# MegaBot.net
KiCad netlist of a schematic drawn in EAGLE
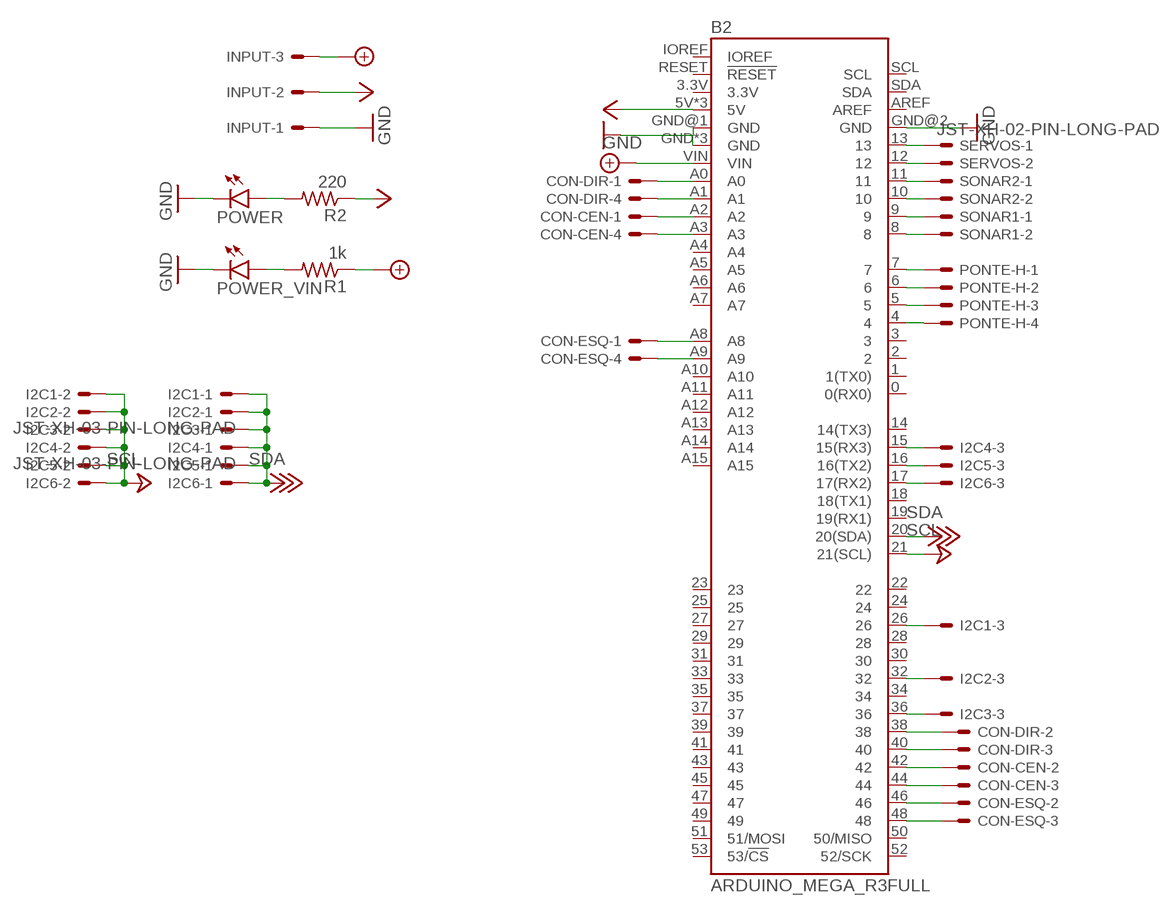
[diagram p0: schematic, sheet 1]

(export (version "E")
  (design (tool "Eeschema 10.0.6"))
  (components
    (comp (ref "B2")
      (value "ARDUINO_MEGA_R3FULL")
      (footprint "eagle-import:ARDUINO_MEGA_NO_SILK")
      (libsource (lib "eagle-import") (part "ARDUINO_MEGA_R3FULL"))
    )
    (comp (ref "CON-CEN")
      (value "JST-XH-04-PIN-LONG-PAD")
      (footprint "eagle-import:JST-XH-04-PACKAGE-LONG-PAD")
      (libsource (lib "eagle-import") (part "JST-XH-04-PIN-LONG-PAD"))
    )
    (comp (ref "CON-DIR")
      (value "JST-XH-04-PIN-LONG-PAD")
      (footprint "eagle-import:JST-XH-04-PACKAGE-LONG-PAD")
      (libsource (lib "eagle-import") (part "JST-XH-04-PIN-LONG-PAD"))
    )
    (comp (ref "CON-ESQ")
      (value "JST-XH-04-PIN-LONG-PAD")
      (footprint "eagle-import:JST-XH-04-PACKAGE-LONG-PAD")
      (libsource (lib "eagle-import") (part "JST-XH-04-PIN-LONG-PAD"))
    )
    (comp (ref "I2C1")
      (value "JST-XH-03-PIN-LONG-PAD")
      (footprint "eagle-import:JST-XH-03-PACKAGE-LONG-PAD")
      (libsource (lib "eagle-import") (part "JST-XH-03-PIN-LONG-PAD"))
    )
    (comp (ref "I2C2")
      (value "JST-XH-03-PIN-LONG-PAD")
      (footprint "eagle-import:JST-XH-03-PACKAGE-LONG-PAD")
      (libsource (lib "eagle-import") (part "JST-XH-03-PIN-LONG-PAD"))
    )
    (comp (ref "I2C3")
      (value "JST-XH-03-PIN-LONG-PAD")
      (footprint "eagle-import:JST-XH-03-PACKAGE-LONG-PAD")
      (libsource (lib "eagle-import") (part "JST-XH-03-PIN-LONG-PAD"))
    )
    (comp (ref "I2C4")
      (value "JST-XH-03-PIN-LONG-PAD")
      (footprint "eagle-import:JST-XH-03-PACKAGE-LONG-PAD")
      (libsource (lib "eagle-import") (part "JST-XH-03-PIN-LONG-PAD"))
    )
    (comp (ref "I2C5")
      (value "JST-XH-03-PIN-LONG-PAD")
      (footprint "eagle-import:JST-XH-03-PACKAGE-LONG-PAD")
      (libsource (lib "eagle-import") (part "JST-XH-03-PIN-LONG-PAD"))
    )
    (comp (ref "I2C6")
      (value "JST-XH-03-PIN-LONG-PAD")
      (footprint "eagle-import:JST-XH-03-PACKAGE-LONG-PAD")
      (libsource (lib "eagle-import") (part "JST-XH-03-PIN-LONG-PAD"))
    )
    (comp (ref "INPUT")
      (value "KK-156-3")
      (footprint "eagle-import:KK-156-3")
      (fields (field (name "MF") "MOLEX"))
      (libsource (lib "eagle-import") (part "KK-156-3"))
    )
    (comp (ref "PONTE-H")
      (value "JST-XH-04-PIN-LONG-PAD")
      (footprint "eagle-import:JST-XH-04-PACKAGE-LONG-PAD")
      (libsource (lib "eagle-import") (part "JST-XH-04-PIN-LONG-PAD"))
    )
    (comp (ref "POWER")
      (value "LEDLED5MM_LONG_PAD")
      (footprint "eagle-import:LED5MM_LONG_PAD")
      (libsource (lib "eagle-import") (part "LEDLED5MM_LONG_PAD"))
    )
    (comp (ref "POWER_VIN")
      (value "LEDLED5MM_LONG_PAD")
      (footprint "eagle-import:LED5MM_LONG_PAD")
      (libsource (lib "eagle-import") (part "LEDLED5MM_LONG_PAD"))
    )
    (comp (ref "R1")
      (value "1k")
      (footprint "eagle-import:0204_7")
      (libsource (lib "eagle-import") (part "R-US_0204/7"))
    )
    (comp (ref "R2")
      (value "220")
      (footprint "eagle-import:0204_7")
      (libsource (lib "eagle-import") (part "R-US_0204/7"))
    )
    (comp (ref "SERVOS")
      (value "JST-XH-02-PIN-LONG-PAD")
      (footprint "eagle-import:JST-XH-02-PACKAGE-LONG-PAD")
      (libsource (lib "eagle-import") (part "JST-XH-02-PIN-LONG-PAD"))
    )
    (comp (ref "SONAR1")
      (value "JST-XH-02-PIN-LONG-PAD")
      (footprint "eagle-import:JST-XH-02-PACKAGE-LONG-PAD")
      (libsource (lib "eagle-import") (part "JST-XH-02-PIN-LONG-PAD"))
    )
    (comp (ref "SONAR2")
      (value "JST-XH-02-PIN-LONG-PAD")
      (footprint "eagle-import:JST-XH-02-PACKAGE-LONG-PAD")
      (libsource (lib "eagle-import") (part "JST-XH-02-PIN-LONG-PAD"))
    )
  )
  (nets
    (net (code "1") (name "+8V") (class "Default")
      (node (ref "B2") (pin "VIN") (pinfunction "VIN_VIN") (pintype "bidirectional"))
      (node (ref "INPUT") (pin "3") (pinfunction "S_3") (pintype "passive"))
      (node (ref "R1") (pin "1") (pinfunction "1_1") (pintype "passive"))
    )
    (net (code "2") (name "GND") (class "Default")
      (node (ref "B2") (pin "GND") (pinfunction "GND_GND") (pintype "bidirectional"))
      (node (ref "B2") (pin "GND@1") (pinfunction "GND_GND@1") (pintype "bidirectional"))
      (node (ref "B2") (pin "GND@2") (pinfunction "GND_GND@2") (pintype "bidirectional"))
      (node (ref "B2") (pin "GND@3") (pinfunction "GND_GND@3") (pintype "bidirectional"))
      (node (ref "B2") (pin "GND@4") (pinfunction "GND_GND@4") (pintype "bidirectional"))
      (node (ref "INPUT") (pin "1") (pinfunction "S_1") (pintype "passive"))
      (node (ref "POWER") (pin "K") (pinfunction "C_K") (pintype "passive"))
      (node (ref "POWER_VIN") (pin "K") (pinfunction "C_K") (pintype "passive"))
    )
    (net (code "3") (name "Net-(B2-15(RX3))") (class "Default")
      (node (ref "B2") (pin "15") (pinfunction "15(RX3)_15") (pintype "bidirectional"))
      (node (ref "I2C4") (pin "3") (pinfunction "S_3") (pintype "passive"))
    )
    (net (code "4") (name "Net-(B2-16(TX2))") (class "Default")
      (node (ref "B2") (pin "16") (pinfunction "16(TX2)_16") (pintype "bidirectional"))
      (node (ref "I2C5") (pin "3") (pinfunction "S_3") (pintype "passive"))
    )
    (net (code "5") (name "Net-(B2-17(RX2))") (class "Default")
      (node (ref "B2") (pin "17") (pinfunction "17(RX2)_17") (pintype "bidirectional"))
      (node (ref "I2C6") (pin "3") (pinfunction "S_3") (pintype "passive"))
    )
    (net (code "6") (name "Net-(CON-CENA-S)") (class "Default")
      (node (ref "B2") (pin "A2") (pinfunction "A2_A2") (pintype "bidirectional"))
      (node (ref "CON-CEN") (pin "1") (pinfunction "S_1") (pintype "passive"))
    )
    (net (code "7") (name "Net-(CON-CENB-S)") (class "Default")
      (node (ref "B2") (pin "42") (pinfunction "42_42") (pintype "bidirectional"))
      (node (ref "CON-CEN") (pin "2") (pinfunction "S_2") (pintype "passive"))
    )
    (net (code "8") (name "Net-(CON-CENC-S)") (class "Default")
      (node (ref "B2") (pin "44") (pinfunction "44_44") (pintype "bidirectional"))
      (node (ref "CON-CEN") (pin "3") (pinfunction "S_3") (pintype "passive"))
    )
    (net (code "9") (name "Net-(CON-CEND-S)") (class "Default")
      (node (ref "B2") (pin "A3") (pinfunction "A3_A3") (pintype "bidirectional"))
      (node (ref "CON-CEN") (pin "4") (pinfunction "S_4") (pintype "passive"))
    )
    (net (code "10") (name "Net-(CON-DIRA-S)") (class "Default")
      (node (ref "B2") (pin "A0") (pinfunction "A0_A0") (pintype "bidirectional"))
      (node (ref "CON-DIR") (pin "1") (pinfunction "S_1") (pintype "passive"))
    )
    (net (code "11") (name "Net-(CON-DIRB-S)") (class "Default")
      (node (ref "B2") (pin "38") (pinfunction "38_38") (pintype "bidirectional"))
      (node (ref "CON-DIR") (pin "2") (pinfunction "S_2") (pintype "passive"))
    )
    (net (code "12") (name "Net-(CON-DIRC-S)") (class "Default")
      (node (ref "B2") (pin "40") (pinfunction "40_40") (pintype "bidirectional"))
      (node (ref "CON-DIR") (pin "3") (pinfunction "S_3") (pintype "passive"))
    )
    (net (code "13") (name "Net-(CON-DIRD-S)") (class "Default")
      (node (ref "B2") (pin "A1") (pinfunction "A1_A1") (pintype "bidirectional"))
      (node (ref "CON-DIR") (pin "4") (pinfunction "S_4") (pintype "passive"))
    )
    (net (code "14") (name "Net-(CON-ESQA-S)") (class "Default")
      (node (ref "B2") (pin "A8") (pinfunction "A8_A8") (pintype "bidirectional"))
      (node (ref "CON-ESQ") (pin "1") (pinfunction "S_1") (pintype "passive"))
    )
    (net (code "15") (name "Net-(CON-ESQB-S)") (class "Default")
      (node (ref "B2") (pin "46") (pinfunction "46_46") (pintype "bidirectional"))
      (node (ref "CON-ESQ") (pin "2") (pinfunction "S_2") (pintype "passive"))
    )
    (net (code "16") (name "Net-(CON-ESQC-S)") (class "Default")
      (node (ref "B2") (pin "48") (pinfunction "48_48") (pintype "bidirectional"))
      (node (ref "CON-ESQ") (pin "3") (pinfunction "S_3") (pintype "passive"))
    )
    (net (code "17") (name "Net-(CON-ESQD-S)") (class "Default")
      (node (ref "B2") (pin "A9") (pinfunction "A9_A9") (pintype "bidirectional"))
      (node (ref "CON-ESQ") (pin "4") (pinfunction "S_4") (pintype "passive"))
    )
    (net (code "18") (name "Net-(I2C1C-S)") (class "Default")
      (node (ref "B2") (pin "26") (pinfunction "26_26") (pintype "bidirectional"))
      (node (ref "I2C1") (pin "3") (pinfunction "S_3") (pintype "passive"))
    )
    (net (code "19") (name "Net-(I2C2C-S)") (class "Default")
      (node (ref "B2") (pin "32") (pinfunction "32_32") (pintype "bidirectional"))
      (node (ref "I2C2") (pin "3") (pinfunction "S_3") (pintype "passive"))
    )
    (net (code "20") (name "Net-(I2C3C-S)") (class "Default")
      (node (ref "B2") (pin "36") (pinfunction "36_36") (pintype "bidirectional"))
      (node (ref "I2C3") (pin "3") (pinfunction "S_3") (pintype "passive"))
    )
    (net (code "21") (name "Net-(PONTE-HA-S)") (class "Default")
      (node (ref "B2") (pin "7") (pinfunction "7_7") (pintype "bidirectional"))
      (node (ref "PONTE-H") (pin "1") (pinfunction "S_1") (pintype "passive"))
    )
    (net (code "22") (name "Net-(PONTE-HB-S)") (class "Default")
      (node (ref "B2") (pin "6") (pinfunction "6_6") (pintype "bidirectional"))
      (node (ref "PONTE-H") (pin "2") (pinfunction "S_2") (pintype "passive"))
    )
    (net (code "23") (name "Net-(PONTE-HC-S)") (class "Default")
      (node (ref "B2") (pin "5") (pinfunction "5_5") (pintype "bidirectional"))
      (node (ref "PONTE-H") (pin "3") (pinfunction "S_3") (pintype "passive"))
    )
    (net (code "24") (name "Net-(PONTE-HD-S)") (class "Default")
      (node (ref "B2") (pin "4") (pinfunction "4_4") (pintype "bidirectional"))
      (node (ref "PONTE-H") (pin "4") (pinfunction "S_4") (pintype "passive"))
    )
    (net (code "25") (name "Net-(POWER-PadA)") (class "Default")
      (node (ref "POWER") (pin "A") (pinfunction "A_A") (pintype "passive"))
      (node (ref "R2") (pin "2") (pinfunction "2_2") (pintype "passive"))
    )
    (net (code "26") (name "Net-(POWER_VIN-PadA)") (class "Default")
      (node (ref "POWER_VIN") (pin "A") (pinfunction "A_A") (pintype "passive"))
      (node (ref "R1") (pin "2") (pinfunction "2_2") (pintype "passive"))
    )
    (net (code "27") (name "Net-(SERVOSA-S)") (class "Default")
      (node (ref "B2") (pin "13") (pinfunction "13_13") (pintype "bidirectional"))
      (node (ref "SERVOS") (pin "1") (pinfunction "S_1") (pintype "passive"))
    )
    (net (code "28") (name "Net-(SERVOSB-S)") (class "Default")
      (node (ref "B2") (pin "12") (pinfunction "12_12") (pintype "bidirectional"))
      (node (ref "SERVOS") (pin "2") (pinfunction "S_2") (pintype "passive"))
    )
    (net (code "29") (name "Net-(SONAR1A-S)") (class "Default")
      (node (ref "B2") (pin "9") (pinfunction "9_9") (pintype "bidirectional"))
      (node (ref "SONAR1") (pin "1") (pinfunction "S_1") (pintype "passive"))
    )
    (net (code "30") (name "Net-(SONAR1B-S)") (class "Default")
      (node (ref "B2") (pin "8") (pinfunction "8_8") (pintype "bidirectional"))
      (node (ref "SONAR1") (pin "2") (pinfunction "S_2") (pintype "passive"))
    )
    (net (code "31") (name "Net-(SONAR2A-S)") (class "Default")
      (node (ref "B2") (pin "11") (pinfunction "11_11") (pintype "bidirectional"))
      (node (ref "SONAR2") (pin "1") (pinfunction "S_1") (pintype "passive"))
    )
    (net (code "32") (name "Net-(SONAR2B-S)") (class "Default")
      (node (ref "B2") (pin "10") (pinfunction "10_10") (pintype "bidirectional"))
      (node (ref "SONAR2") (pin "2") (pinfunction "S_2") (pintype "passive"))
    )
    (net (code "33") (name "SCL") (class "Default")
      (node (ref "B2") (pin "21") (pinfunction "21(SCL)_21") (pintype "bidirectional"))
      (node (ref "I2C1") (pin "2") (pinfunction "S_2") (pintype "passive"))
      (node (ref "I2C2") (pin "2") (pinfunction "S_2") (pintype "passive"))
      (node (ref "I2C3") (pin "2") (pinfunction "S_2") (pintype "passive"))
      (node (ref "I2C4") (pin "2") (pinfunction "S_2") (pintype "passive"))
      (node (ref "I2C5") (pin "2") (pinfunction "S_2") (pintype "passive"))
      (node (ref "I2C6") (pin "2") (pinfunction "S_2") (pintype "passive"))
    )
    (net (code "34") (name "SDA") (class "Default")
      (node (ref "B2") (pin "20") (pinfunction "20(SDA)_20") (pintype "bidirectional"))
      (node (ref "I2C1") (pin "1") (pinfunction "S_1") (pintype "passive"))
      (node (ref "I2C2") (pin "1") (pinfunction "S_1") (pintype "passive"))
      (node (ref "I2C3") (pin "1") (pinfunction "S_1") (pintype "passive"))
      (node (ref "I2C4") (pin "1") (pinfunction "S_1") (pintype "passive"))
      (node (ref "I2C5") (pin "1") (pinfunction "S_1") (pintype "passive"))
      (node (ref "I2C6") (pin "1") (pinfunction "S_1") (pintype "passive"))
    )
    (net (code "35") (name "VCC") (class "Default")
      (node (ref "B2") (pin "5V") (pinfunction "5V_5V") (pintype "bidirectional"))
      (node (ref "B2") (pin "5V@1") (pinfunction "5V_5V@1") (pintype "bidirectional"))
      (node (ref "B2") (pin "5V@2") (pinfunction "5V_5V@2") (pintype "bidirectional"))
      (node (ref "INPUT") (pin "2") (pinfunction "S_2") (pintype "passive"))
      (node (ref "R2") (pin "1") (pinfunction "1_1") (pintype "passive"))
    )
    (net (code "36") (name "unconnected-(B2-0(RX0)-Pad0)") (class "Default")
      (node (ref "B2") (pin "0") (pinfunction "0(RX0)_0") (pintype "bidirectional"))
    )
    (net (code "37") (name "unconnected-(B2-1(TX0)-Pad1)") (class "Default")
      (node (ref "B2") (pin "1") (pinfunction "1(TX0)_1") (pintype "bidirectional"))
    )
    (net (code "38") (name "unconnected-(B2-14(TX3)-Pad14)") (class "Default")
      (node (ref "B2") (pin "14") (pinfunction "14(TX3)_14") (pintype "bidirectional"))
    )
    (net (code "39") (name "unconnected-(B2-18(TX1)-Pad18)") (class "Default")
      (node (ref "B2") (pin "18") (pinfunction "18(TX1)_18") (pintype "bidirectional"))
    )
    (net (code "40") (name "unconnected-(B2-19(RX1)-Pad19)") (class "Default")
      (node (ref "B2") (pin "19") (pinfunction "19(RX1)_19") (pintype "bidirectional"))
    )
    (net (code "41") (name "unconnected-(B2-50{slash}MISO-Pad50)") (class "Default")
      (node (ref "B2") (pin "50") (pinfunction "50/MISO_50") (pintype "bidirectional"))
    )
    (net (code "42") (name "unconnected-(B2-51{slash}MOSI-Pad51)") (class "Default")
      (node (ref "B2") (pin "51") (pinfunction "51/MOSI_51") (pintype "bidirectional"))
    )
    (net (code "43") (name "unconnected-(B2-52{slash}SCK-Pad52)") (class "Default")
      (node (ref "B2") (pin "52") (pinfunction "52/SCK_52") (pintype "bidirectional"))
    )
    (net (code "44") (name "unconnected-(B2-53{slash}~{CS}-Pad53)") (class "Default")
      (node (ref "B2") (pin "53") (pinfunction "53/~{CS}_53") (pintype "bidirectional"))
    )
    (net (code "45") (name "unconnected-(B2-Pad2)") (class "Default")
      (node (ref "B2") (pin "2") (pinfunction "2_2") (pintype "bidirectional"))
    )
    (net (code "46") (name "unconnected-(B2-Pad3)") (class "Default")
      (node (ref "B2") (pin "3") (pinfunction "3_3") (pintype "bidirectional"))
    )
    (net (code "47") (name "unconnected-(B2-Pad3.3V)") (class "Default")
      (node (ref "B2") (pin "3.3V") (pinfunction "3.3V_3.3V") (pintype "bidirectional"))
    )
    (net (code "48") (name "unconnected-(B2-Pad22)") (class "Default")
      (node (ref "B2") (pin "22") (pinfunction "22_22") (pintype "bidirectional"))
    )
    (net (code "49") (name "unconnected-(B2-Pad23)") (class "Default")
      (node (ref "B2") (pin "23") (pinfunction "23_23") (pintype "bidirectional"))
    )
    (net (code "50") (name "unconnected-(B2-Pad24)") (class "Default")
      (node (ref "B2") (pin "24") (pinfunction "24_24") (pintype "bidirectional"))
    )
    (net (code "51") (name "unconnected-(B2-Pad25)") (class "Default")
      (node (ref "B2") (pin "25") (pinfunction "25_25") (pintype "bidirectional"))
    )
    (net (code "52") (name "unconnected-(B2-Pad27)") (class "Default")
      (node (ref "B2") (pin "27") (pinfunction "27_27") (pintype "bidirectional"))
    )
    (net (code "53") (name "unconnected-(B2-Pad28)") (class "Default")
      (node (ref "B2") (pin "28") (pinfunction "28_28") (pintype "bidirectional"))
    )
    (net (code "54") (name "unconnected-(B2-Pad29)") (class "Default")
      (node (ref "B2") (pin "29") (pinfunction "29_29") (pintype "bidirectional"))
    )
    (net (code "55") (name "unconnected-(B2-Pad30)") (class "Default")
      (node (ref "B2") (pin "30") (pinfunction "30_30") (pintype "bidirectional"))
    )
    (net (code "56") (name "unconnected-(B2-Pad31)") (class "Default")
      (node (ref "B2") (pin "31") (pinfunction "31_31") (pintype "bidirectional"))
    )
    (net (code "57") (name "unconnected-(B2-Pad33)") (class "Default")
      (node (ref "B2") (pin "33") (pinfunction "33_33") (pintype "bidirectional"))
    )
    (net (code "58") (name "unconnected-(B2-Pad34)") (class "Default")
      (node (ref "B2") (pin "34") (pinfunction "34_34") (pintype "bidirectional"))
    )
    (net (code "59") (name "unconnected-(B2-Pad35)") (class "Default")
      (node (ref "B2") (pin "35") (pinfunction "35_35") (pintype "bidirectional"))
    )
    (net (code "60") (name "unconnected-(B2-Pad37)") (class "Default")
      (node (ref "B2") (pin "37") (pinfunction "37_37") (pintype "bidirectional"))
    )
    (net (code "61") (name "unconnected-(B2-Pad39)") (class "Default")
      (node (ref "B2") (pin "39") (pinfunction "39_39") (pintype "bidirectional"))
    )
    (net (code "62") (name "unconnected-(B2-Pad41)") (class "Default")
      (node (ref "B2") (pin "41") (pinfunction "41_41") (pintype "bidirectional"))
    )
    (net (code "63") (name "unconnected-(B2-Pad43)") (class "Default")
      (node (ref "B2") (pin "43") (pinfunction "43_43") (pintype "bidirectional"))
    )
    (net (code "64") (name "unconnected-(B2-Pad45)") (class "Default")
      (node (ref "B2") (pin "45") (pinfunction "45_45") (pintype "bidirectional"))
    )
    (net (code "65") (name "unconnected-(B2-Pad47)") (class "Default")
      (node (ref "B2") (pin "47") (pinfunction "47_47") (pintype "bidirectional"))
    )
    (net (code "66") (name "unconnected-(B2-Pad49)") (class "Default")
      (node (ref "B2") (pin "49") (pinfunction "49_49") (pintype "bidirectional"))
    )
    (net (code "67") (name "unconnected-(B2-PadA4)") (class "Default")
      (node (ref "B2") (pin "A4") (pinfunction "A4_A4") (pintype "bidirectional"))
    )
    (net (code "68") (name "unconnected-(B2-PadA5)") (class "Default")
      (node (ref "B2") (pin "A5") (pinfunction "A5_A5") (pintype "bidirectional"))
    )
    (net (code "69") (name "unconnected-(B2-PadA6)") (class "Default")
      (node (ref "B2") (pin "A6") (pinfunction "A6_A6") (pintype "bidirectional"))
    )
    (net (code "70") (name "unconnected-(B2-PadA7)") (class "Default")
      (node (ref "B2") (pin "A7") (pinfunction "A7_A7") (pintype "bidirectional"))
    )
    (net (code "71") (name "unconnected-(B2-PadA10)") (class "Default")
      (node (ref "B2") (pin "A10") (pinfunction "A10_A10") (pintype "bidirectional"))
    )
    (net (code "72") (name "unconnected-(B2-PadA11)") (class "Default")
      (node (ref "B2") (pin "A11") (pinfunction "A11_A11") (pintype "bidirectional"))
    )
    (net (code "73") (name "unconnected-(B2-PadA12)") (class "Default")
      (node (ref "B2") (pin "A12") (pinfunction "A12_A12") (pintype "bidirectional"))
    )
    (net (code "74") (name "unconnected-(B2-PadA13)") (class "Default")
      (node (ref "B2") (pin "A13") (pinfunction "A13_A13") (pintype "bidirectional"))
    )
    (net (code "75") (name "unconnected-(B2-PadA14)") (class "Default")
      (node (ref "B2") (pin "A14") (pinfunction "A14_A14") (pintype "bidirectional"))
    )
    (net (code "76") (name "unconnected-(B2-PadA15)") (class "Default")
      (node (ref "B2") (pin "A15") (pinfunction "A15_A15") (pintype "bidirectional"))
    )
    (net (code "77") (name "unconnected-(B2-PadAREF)") (class "Default")
      (node (ref "B2") (pin "AREF") (pinfunction "AREF_AREF") (pintype "bidirectional"))
    )
    (net (code "78") (name "unconnected-(B2-PadIOREF)") (class "Default")
      (node (ref "B2") (pin "IOREF") (pinfunction "IOREF_IOREF") (pintype "bidirectional"))
    )
    (net (code "79") (name "unconnected-(B2-PadSCL)") (class "Default")
      (node (ref "B2") (pin "SCL") (pinfunction "SCL_SCL") (pintype "bidirectional"))
    )
    (net (code "80") (name "unconnected-(B2-PadSDA)") (class "Default")
      (node (ref "B2") (pin "SDA") (pinfunction "SDA_SDA") (pintype "bidirectional"))
    )
    (net (code "81") (name "unconnected-(B2-~{RESET}-PadRESET)") (class "Default")
      (node (ref "B2") (pin "RESET") (pinfunction "~{RESET}_RESET") (pintype "bidirectional"))
    )
  )
)
